# harvester_hat.net
KiCad netlist of a schematic drawn in EAGLE
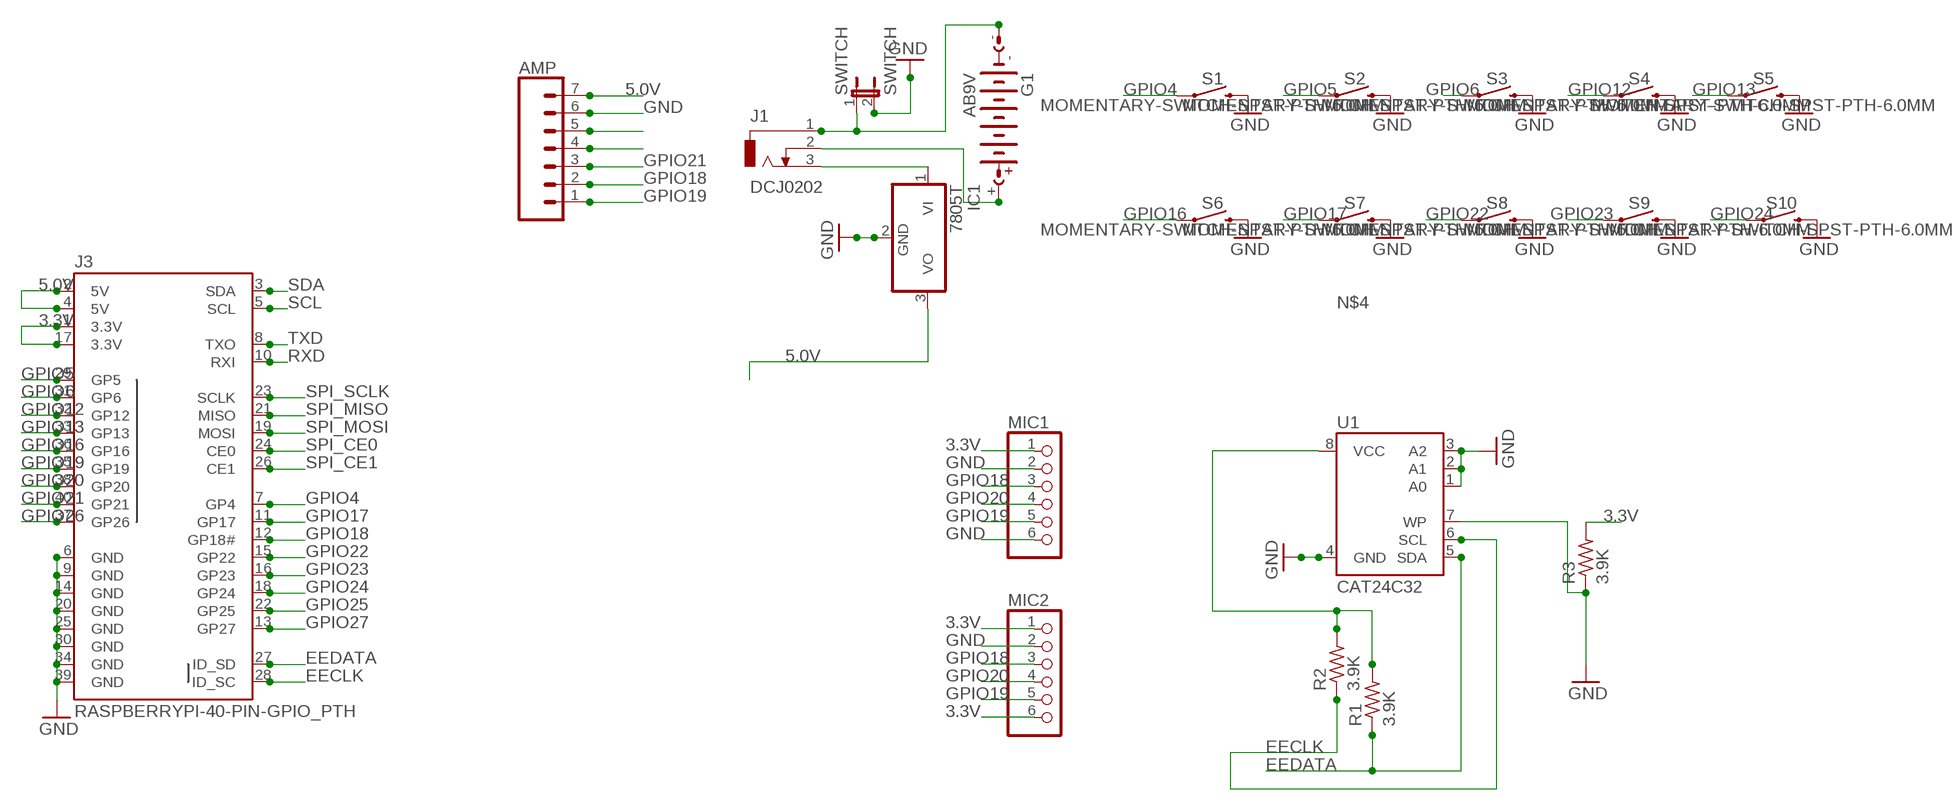
[diagram p0: schematic, sheet 1]

(export (version "E")
  (design (tool "Eeschema 10.0.6"))
  (components
    (comp (ref "AMP")
      (value "CONN_07")
      (footprint "eagle-import:1X07")
      (libsource (lib "eagle-import") (part "CONN_07"))
    )
    (comp (ref "G1")
      (value "AB9V")
      (footprint "eagle-import:AB9V")
      (libsource (lib "eagle-import") (part "AB9V"))
    )
    (comp (ref "IC1")
      (value "7805T")
      (footprint "eagle-import:TO220H")
      (libsource (lib "eagle-import") (part "78T05"))
    )
    (comp (ref "J1")
      (value "DCJ0202")
      (footprint "eagle-import:DCJ0202")
      (libsource (lib "eagle-import") (part "DCJ0202"))
    )
    (comp (ref "J3")
      (value "RASPBERRYPI-40-PIN-GPIO_PTH")
      (footprint "eagle-import:2X20_SHROUDED")
      (libsource (lib "eagle-import") (part "RASPBERRYPI-40-PIN-GPIO_PTH"))
    )
    (comp (ref "MIC1")
      (value "PINHD-1X6")
      (footprint "eagle-import:1X06")
      (libsource (lib "eagle-import") (part "PINHD-1X6"))
    )
    (comp (ref "MIC2")
      (value "PINHD-1X6")
      (footprint "eagle-import:1X06")
      (libsource (lib "eagle-import") (part "PINHD-1X6"))
    )
    (comp (ref "R1")
      (value "3.9K")
      (footprint "eagle-import:0207_10")
      (libsource (lib "eagle-import") (part "R-US_0207/10"))
    )
    (comp (ref "R2")
      (value "3.9K")
      (footprint "eagle-import:0207_10")
      (libsource (lib "eagle-import") (part "R-US_0207/10"))
    )
    (comp (ref "R3")
      (value "3.9K")
      (footprint "eagle-import:0207_10")
      (libsource (lib "eagle-import") (part "R-US_0207/10"))
    )
    (comp (ref "S1")
      (value "MOMENTARY-SWITCH-SPST-PTH-6.0MM")
      (footprint "eagle-import:TACTILE_SWITCH_PTH_6.0MM")
      (libsource (lib "eagle-import") (part "MOMENTARY-SWITCH-SPST-PTH-6.0MM"))
    )
    (comp (ref "S2")
      (value "MOMENTARY-SWITCH-SPST-PTH-6.0MM")
      (footprint "eagle-import:TACTILE_SWITCH_PTH_6.0MM")
      (libsource (lib "eagle-import") (part "MOMENTARY-SWITCH-SPST-PTH-6.0MM"))
    )
    (comp (ref "S3")
      (value "MOMENTARY-SWITCH-SPST-PTH-6.0MM")
      (footprint "eagle-import:TACTILE_SWITCH_PTH_6.0MM")
      (libsource (lib "eagle-import") (part "MOMENTARY-SWITCH-SPST-PTH-6.0MM"))
    )
    (comp (ref "S4")
      (value "MOMENTARY-SWITCH-SPST-PTH-6.0MM")
      (footprint "eagle-import:TACTILE_SWITCH_PTH_6.0MM")
      (libsource (lib "eagle-import") (part "MOMENTARY-SWITCH-SPST-PTH-6.0MM"))
    )
    (comp (ref "S5")
      (value "MOMENTARY-SWITCH-SPST-PTH-6.0MM")
      (footprint "eagle-import:TACTILE_SWITCH_PTH_6.0MM")
      (libsource (lib "eagle-import") (part "MOMENTARY-SWITCH-SPST-PTH-6.0MM"))
    )
    (comp (ref "S6")
      (value "MOMENTARY-SWITCH-SPST-PTH-6.0MM")
      (footprint "eagle-import:TACTILE_SWITCH_PTH_6.0MM")
      (libsource (lib "eagle-import") (part "MOMENTARY-SWITCH-SPST-PTH-6.0MM"))
    )
    (comp (ref "S7")
      (value "MOMENTARY-SWITCH-SPST-PTH-6.0MM")
      (footprint "eagle-import:TACTILE_SWITCH_PTH_6.0MM")
      (libsource (lib "eagle-import") (part "MOMENTARY-SWITCH-SPST-PTH-6.0MM"))
    )
    (comp (ref "S8")
      (value "MOMENTARY-SWITCH-SPST-PTH-6.0MM")
      (footprint "eagle-import:TACTILE_SWITCH_PTH_6.0MM")
      (libsource (lib "eagle-import") (part "MOMENTARY-SWITCH-SPST-PTH-6.0MM"))
    )
    (comp (ref "S9")
      (value "MOMENTARY-SWITCH-SPST-PTH-6.0MM")
      (footprint "eagle-import:TACTILE_SWITCH_PTH_6.0MM")
      (libsource (lib "eagle-import") (part "MOMENTARY-SWITCH-SPST-PTH-6.0MM"))
    )
    (comp (ref "S10")
      (value "MOMENTARY-SWITCH-SPST-PTH-6.0MM")
      (footprint "eagle-import:TACTILE_SWITCH_PTH_6.0MM")
      (libsource (lib "eagle-import") (part "MOMENTARY-SWITCH-SPST-PTH-6.0MM"))
    )
    (comp (ref "SWITCH")
      (value "SWITCH")
      (footprint "eagle-import:JP1")
      (libsource (lib "eagle-import") (part "JP1E"))
    )
    (comp (ref "U1")
      (value "CAT24C32")
      (footprint "eagle-import:DIL08")
      (fields (field (name "MPN") "AT24C1024BW-SH-B"))
      (libsource (lib "eagle-import") (part "AT24CP"))
    )
  )
  (nets
    (net (code "1") (name "/3.3V") (class "Default")
      (node (ref "J3") (pin "1") (pinfunction "3.3V_1") (pintype "power_in"))
      (node (ref "J3") (pin "17") (pinfunction "3.3V_17") (pintype "power_in"))
      (node (ref "MIC1") (pin "1") (pinfunction "1_1") (pintype "passive"))
      (node (ref "MIC2") (pin "1") (pinfunction "1_1") (pintype "passive"))
      (node (ref "MIC2") (pin "6") (pinfunction "6_6") (pintype "passive"))
      (node (ref "R3") (pin "2") (pinfunction "2_2") (pintype "passive"))
    )
    (net (code "2") (name "/5.0V") (class "Default")
      (node (ref "AMP") (pin "7") (pinfunction "7_7") (pintype "passive"))
      (node (ref "IC1") (pin "3") (pinfunction "VO_3") (pintype "passive"))
      (node (ref "J3") (pin "2") (pinfunction "5V_2") (pintype "power_in"))
      (node (ref "J3") (pin "4") (pinfunction "5V_4") (pintype "power_in"))
    )
    (net (code "3") (name "/EECLK") (class "Default")
      (node (ref "J3") (pin "28") (pinfunction "ID_SC_28") (pintype "bidirectional"))
      (node (ref "R2") (pin "1") (pinfunction "1_1") (pintype "passive"))
      (node (ref "U1") (pin "6") (pinfunction "SCL_6") (pintype "bidirectional"))
    )
    (net (code "4") (name "/EEDATA") (class "Default")
      (node (ref "J3") (pin "27") (pinfunction "ID_SD_27") (pintype "bidirectional"))
      (node (ref "R1") (pin "1") (pinfunction "1_1") (pintype "passive"))
      (node (ref "U1") (pin "5") (pinfunction "SDA_5") (pintype "bidirectional"))
    )
    (net (code "5") (name "/GPIO4") (class "Default")
      (node (ref "J3") (pin "7") (pinfunction "GP4_7") (pintype "bidirectional"))
      (node (ref "S1") (pin "1") (pinfunction "1_1") (pintype "passive"))
    )
    (net (code "6") (name "/GPIO5") (class "Default")
      (node (ref "J3") (pin "29") (pinfunction "GP5_29") (pintype "bidirectional"))
      (node (ref "S2") (pin "1") (pinfunction "1_1") (pintype "passive"))
    )
    (net (code "7") (name "/GPIO6") (class "Default")
      (node (ref "J3") (pin "31") (pinfunction "GP6_31") (pintype "bidirectional"))
      (node (ref "S3") (pin "1") (pinfunction "1_1") (pintype "passive"))
    )
    (net (code "8") (name "/GPIO12") (class "Default")
      (node (ref "J3") (pin "32") (pinfunction "GP12_32") (pintype "bidirectional"))
      (node (ref "S4") (pin "1") (pinfunction "1_1") (pintype "passive"))
    )
    (net (code "9") (name "/GPIO13") (class "Default")
      (node (ref "J3") (pin "33") (pinfunction "GP13_33") (pintype "bidirectional"))
      (node (ref "S5") (pin "1") (pinfunction "1_1") (pintype "passive"))
    )
    (net (code "10") (name "/GPIO16") (class "Default")
      (node (ref "J3") (pin "36") (pinfunction "GP16_36") (pintype "bidirectional"))
      (node (ref "S6") (pin "1") (pinfunction "1_1") (pintype "passive"))
    )
    (net (code "11") (name "/GPIO17") (class "Default")
      (node (ref "J3") (pin "11") (pinfunction "GP17_11") (pintype "bidirectional"))
      (node (ref "S7") (pin "1") (pinfunction "1_1") (pintype "passive"))
    )
    (net (code "12") (name "/GPIO18") (class "Default")
      (node (ref "AMP") (pin "2") (pinfunction "2_2") (pintype "passive"))
      (node (ref "J3") (pin "12") (pinfunction "GP18#_12") (pintype "bidirectional"))
      (node (ref "MIC1") (pin "3") (pinfunction "3_3") (pintype "passive"))
      (node (ref "MIC2") (pin "3") (pinfunction "3_3") (pintype "passive"))
    )
    (net (code "13") (name "/GPIO19") (class "Default")
      (node (ref "AMP") (pin "1") (pinfunction "1_1") (pintype "passive"))
      (node (ref "J3") (pin "35") (pinfunction "GP19_35") (pintype "bidirectional"))
      (node (ref "MIC1") (pin "5") (pinfunction "5_5") (pintype "passive"))
      (node (ref "MIC2") (pin "5") (pinfunction "5_5") (pintype "passive"))
    )
    (net (code "14") (name "/GPIO20") (class "Default")
      (node (ref "J3") (pin "38") (pinfunction "GP20_38") (pintype "bidirectional"))
      (node (ref "MIC1") (pin "4") (pinfunction "4_4") (pintype "passive"))
      (node (ref "MIC2") (pin "4") (pinfunction "4_4") (pintype "passive"))
    )
    (net (code "15") (name "/GPIO21") (class "Default")
      (node (ref "AMP") (pin "3") (pinfunction "3_3") (pintype "passive"))
      (node (ref "J3") (pin "40") (pinfunction "GP21_40") (pintype "bidirectional"))
    )
    (net (code "16") (name "/GPIO22") (class "Default")
      (node (ref "J3") (pin "15") (pinfunction "GP22_15") (pintype "bidirectional"))
      (node (ref "S8") (pin "1") (pinfunction "1_1") (pintype "passive"))
    )
    (net (code "17") (name "/GPIO23") (class "Default")
      (node (ref "J3") (pin "16") (pinfunction "GP23_16") (pintype "bidirectional"))
      (node (ref "S9") (pin "1") (pinfunction "1_1") (pintype "passive"))
    )
    (net (code "18") (name "/GPIO24") (class "Default")
      (node (ref "J3") (pin "18") (pinfunction "GP24_18") (pintype "bidirectional"))
      (node (ref "S10") (pin "1") (pinfunction "1_1") (pintype "passive"))
    )
    (net (code "19") (name "/GPIO25") (class "Default")
      (node (ref "J3") (pin "22") (pinfunction "GP25_22") (pintype "bidirectional"))
    )
    (net (code "20") (name "/GPIO26") (class "Default")
      (node (ref "J3") (pin "37") (pinfunction "GP26_37") (pintype "bidirectional"))
    )
    (net (code "21") (name "/GPIO27") (class "Default")
      (node (ref "J3") (pin "13") (pinfunction "GP27_13") (pintype "bidirectional"))
    )
    (net (code "22") (name "/N$4") (class "Default")
      (node (ref "R1") (pin "2") (pinfunction "2_2") (pintype "passive"))
      (node (ref "R2") (pin "2") (pinfunction "2_2") (pintype "passive"))
      (node (ref "U1") (pin "8") (pinfunction "VCC_8") (pintype "power_in"))
    )
    (net (code "23") (name "/RXD") (class "Default")
      (node (ref "J3") (pin "10") (pinfunction "RXI_10") (pintype "input"))
    )
    (net (code "24") (name "/SCL") (class "Default")
      (node (ref "J3") (pin "5") (pinfunction "SCL_5") (pintype "bidirectional"))
    )
    (net (code "25") (name "/SDA") (class "Default")
      (node (ref "J3") (pin "3") (pinfunction "SDA_3") (pintype "bidirectional"))
    )
    (net (code "26") (name "/SPI_CE0") (class "Default")
      (node (ref "J3") (pin "24") (pinfunction "CE0_24") (pintype "output"))
    )
    (net (code "27") (name "/SPI_CE1") (class "Default")
      (node (ref "J3") (pin "26") (pinfunction "CE1_26") (pintype "output"))
    )
    (net (code "28") (name "/SPI_MISO") (class "Default")
      (node (ref "J3") (pin "21") (pinfunction "MISO_21") (pintype "input"))
    )
    (net (code "29") (name "/SPI_MOSI") (class "Default")
      (node (ref "J3") (pin "19") (pinfunction "MOSI_19") (pintype "output"))
    )
    (net (code "30") (name "/SPI_SCLK") (class "Default")
      (node (ref "J3") (pin "23") (pinfunction "SCLK_23") (pintype "output"))
    )
    (net (code "31") (name "/TXD") (class "Default")
      (node (ref "J3") (pin "8") (pinfunction "TXO_8") (pintype "output"))
    )
    (net (code "32") (name "GND") (class "Default")
      (node (ref "AMP") (pin "6") (pinfunction "6_6") (pintype "passive"))
      (node (ref "IC1") (pin "2") (pinfunction "GND_2") (pintype "passive"))
      (node (ref "J3") (pin "14") (pinfunction "GND_14") (pintype "power_in"))
      (node (ref "J3") (pin "20") (pinfunction "GND_20") (pintype "power_in"))
      (node (ref "J3") (pin "25") (pinfunction "GND_25") (pintype "power_in"))
      (node (ref "J3") (pin "30") (pinfunction "GND_30") (pintype "power_in"))
      (node (ref "J3") (pin "34") (pinfunction "GND_34") (pintype "power_in"))
      (node (ref "J3") (pin "39") (pinfunction "GND_39") (pintype "power_in"))
      (node (ref "J3") (pin "6") (pinfunction "GND_6") (pintype "power_in"))
      (node (ref "J3") (pin "9") (pinfunction "GND_9") (pintype "power_in"))
      (node (ref "MIC1") (pin "2") (pinfunction "2_2") (pintype "passive"))
      (node (ref "MIC1") (pin "6") (pinfunction "6_6") (pintype "passive"))
      (node (ref "MIC2") (pin "2") (pinfunction "2_2") (pintype "passive"))
      (node (ref "R3") (pin "1") (pinfunction "1_1") (pintype "passive"))
      (node (ref "S1") (pin "3") (pinfunction "2_3") (pintype "passive"))
      (node (ref "S10") (pin "3") (pinfunction "2_3") (pintype "passive"))
      (node (ref "S2") (pin "3") (pinfunction "2_3") (pintype "passive"))
      (node (ref "S3") (pin "3") (pinfunction "2_3") (pintype "passive"))
      (node (ref "S4") (pin "3") (pinfunction "2_3") (pintype "passive"))
      (node (ref "S5") (pin "3") (pinfunction "2_3") (pintype "passive"))
      (node (ref "S6") (pin "3") (pinfunction "2_3") (pintype "passive"))
      (node (ref "S7") (pin "3") (pinfunction "2_3") (pintype "passive"))
      (node (ref "S8") (pin "3") (pinfunction "2_3") (pintype "passive"))
      (node (ref "S9") (pin "3") (pinfunction "2_3") (pintype "passive"))
      (node (ref "SWITCH") (pin "2") (pinfunction "2_2") (pintype "passive"))
      (node (ref "U1") (pin "1") (pinfunction "A0_1") (pintype "input"))
      (node (ref "U1") (pin "2") (pinfunction "A1_2") (pintype "input"))
      (node (ref "U1") (pin "3") (pinfunction "A2_3") (pintype "input"))
      (node (ref "U1") (pin "4") (pinfunction "GND_4") (pintype "power_in"))
      (node (ref "U1") (pin "7") (pinfunction "WP_7") (pintype "input"))
    )
    (net (code "33") (name "Net-(G1-Pad+)") (class "Default")
      (node (ref "G1") (pin "+") (pinfunction "+_+") (pintype "passive"))
      (node (ref "J1") (pin "2") (pinfunction "2_2") (pintype "passive"))
    )
    (net (code "34") (name "Net-(G1-Pad-)") (class "Default")
      (node (ref "G1") (pin "-") (pinfunction "-_-") (pintype "passive"))
      (node (ref "J1") (pin "1") (pinfunction "1_1") (pintype "passive"))
      (node (ref "SWITCH") (pin "1") (pinfunction "1_1") (pintype "passive"))
    )
    (net (code "35") (name "Net-(IC1-VI)") (class "Default")
      (node (ref "IC1") (pin "1") (pinfunction "VI_1") (pintype "input"))
      (node (ref "J1") (pin "3") (pinfunction "3_3") (pintype "passive"))
    )
    (net (code "36") (name "unconnected-(AMP-Pad4)") (class "Default")
      (node (ref "AMP") (pin "4") (pinfunction "4_4") (pintype "passive"))
    )
    (net (code "37") (name "unconnected-(AMP-Pad5)") (class "Default")
      (node (ref "AMP") (pin "5") (pinfunction "5_5") (pintype "passive"))
    )
  )
)
